# LCD4_3.net
KiCad netlist of a schematic drawn in Altium Designer
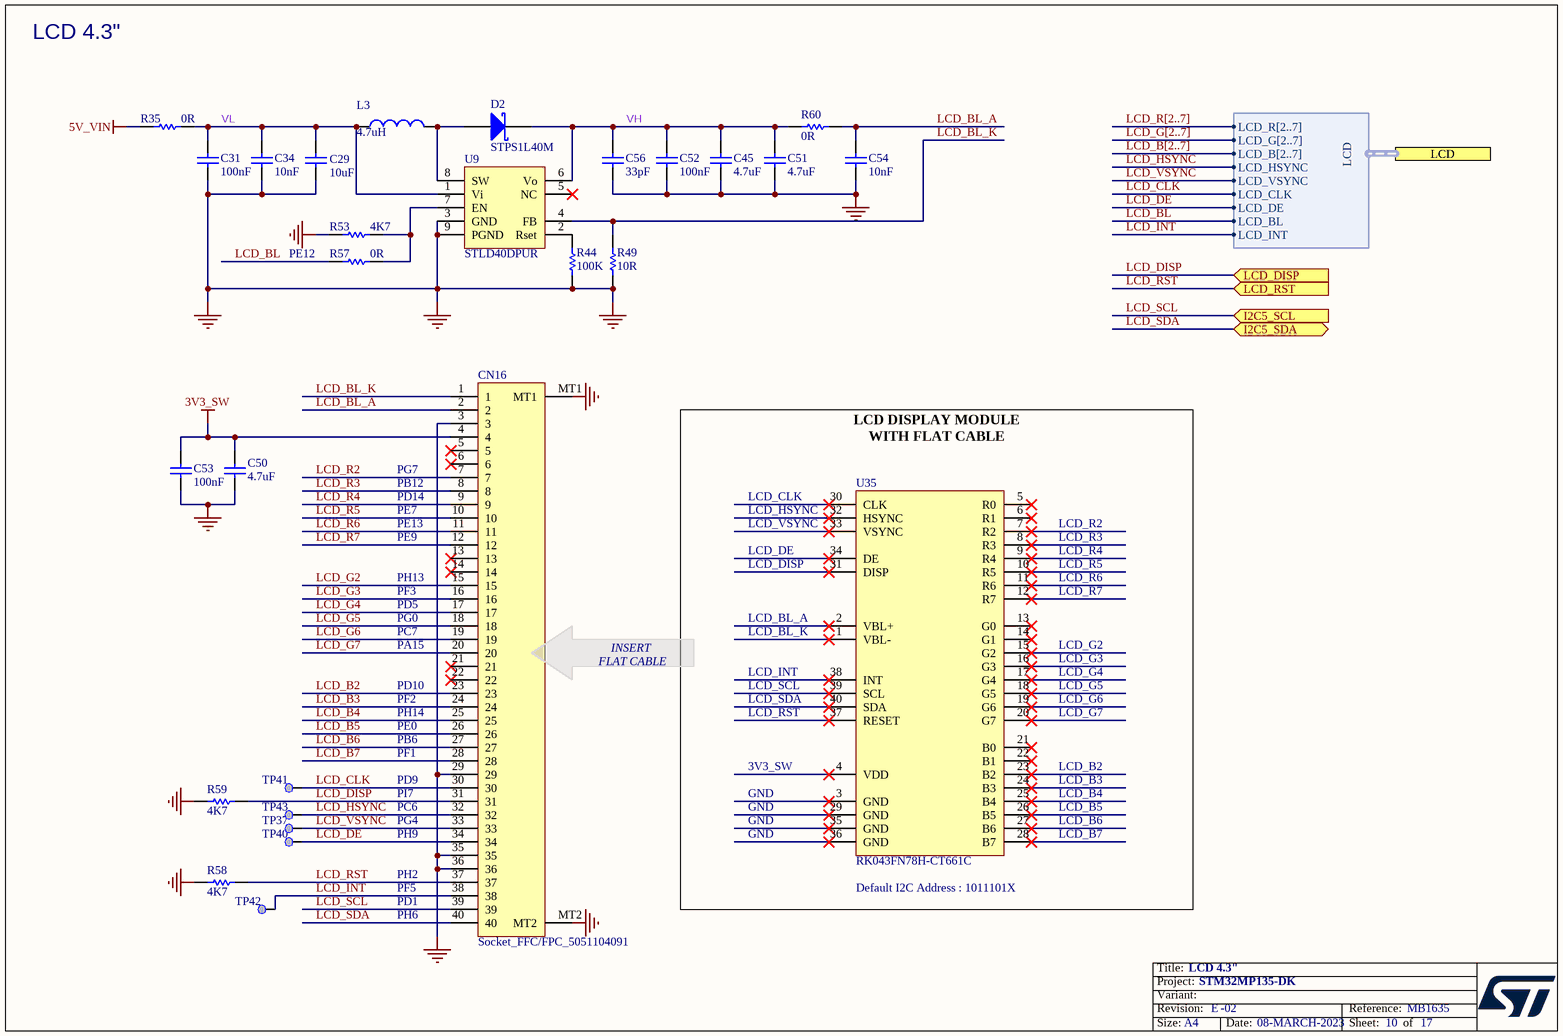
[diagram p0: LCD4.3.SchDoc]

(export (version "E")
  (design (tool "Eeschema 10.0.6"))
  (components
    (comp (ref "C29")
      (value "10uF")
      (footprint "C0603")
      (description "Capacitor, MLCC, 10uF, 10V, X5R, +/-10%, 0603, T=0.8mm")
      (fields
        (field (name "INTERNAL_PART_NUMBER") "MCD-00099")
        (field (name "MANUFACTURER_PART_NUMBER") "GRM188R61A106KE69D")
      )
      (libsource (lib "MCD_PARTS_database") (part "Capacitor"))
    )
    (comp (ref "C31")
      (value "100nF")
      (footprint "C0402")
      (description "Capacitor, MLCC, 100nF, 16V, X7R, +/-10%, 0402, T=0.5mm")
      (fields
        (field (name "INTERNAL_PART_NUMBER") "MCD-00006")
        (field (name "MANUFACTURER_PART_NUMBER") "CC0402KRX7R7BB104")
      )
      (libsource (lib "MCD_PARTS_database") (part "Capacitor"))
    )
    (comp (ref "C34")
      (value "10nF")
      (footprint "C0402")
      (description "Capacitor, MLCC, 10nF, 50V, X7R, +/-10%, 0402, T=0.5mm")
      (fields
        (field (name "INTERNAL_PART_NUMBER") "MCD-02198")
        (field (name "MANUFACTURER_PART_NUMBER") "CC0402KRX7R9BB103")
      )
      (libsource (lib "MCD_PARTS_database") (part "Capacitor"))
    )
    (comp (ref "C45")
      (value "4.7uF")
      (footprint "C1206_H1P25")
      (description "Capacitor, MLCC, 4.7uF, 50V, X7R, +/-10%, 1206, T=1.27mm")
      (fields
        (field (name "INTERNAL_PART_NUMBER") "MCD-00013")
        (field (name "MANUFACTURER_PART_NUMBER") "12065C475KAT2A")
      )
      (libsource (lib "MCD_PARTS_database") (part "Capacitor"))
    )
    (comp (ref "C50")
      (value "4.7uF")
      (footprint "C0402")
      (description "Capacitor, MLCC, 4.7uF, 6V3, X5R, +/-20%, 0402, T=0.5mm")
      (fields
        (field (name "INTERNAL_PART_NUMBER") "MCD-01356")
        (field (name "MANUFACTURER_PART_NUMBER") "GRM155R60J475ME47")
      )
      (libsource (lib "MCD_PARTS_database") (part "Capacitor"))
    )
    (comp (ref "C51")
      (value "4.7uF")
      (footprint "C1206_H1P25")
      (description "Capacitor, MLCC, 4.7uF, 50V, X7R, +/-10%, 1206, T=1.27mm")
      (fields
        (field (name "INTERNAL_PART_NUMBER") "MCD-00013")
        (field (name "MANUFACTURER_PART_NUMBER") "12065C475KAT2A")
      )
      (libsource (lib "MCD_PARTS_database") (part "Capacitor"))
    )
    (comp (ref "C52")
      (value "100nF")
      (footprint "C0603")
      (description "Capacitor, MLCC, 100nF, 50V, X7R, +/-10%, 0603, T=0.8mm")
      (fields (field (name "INTERNAL_PART_NUMBER") "MCD-01099") (field (name "BMS_PART_NUMBER") "9142278"))
      (libsource (lib "MCD_PARTS_database") (part "Capacitor"))
    )
    (comp (ref "C53")
      (value "100nF")
      (footprint "C0402")
      (description "Capacitor, MLCC, 100nF, 16V, X7R, +/-10%, 0402, T=0.5mm")
      (fields
        (field (name "INTERNAL_PART_NUMBER") "MCD-00006")
        (field (name "MANUFACTURER_PART_NUMBER") "CC0402KRX7R7BB104")
      )
      (libsource (lib "MCD_PARTS_database") (part "Capacitor"))
    )
    (comp (ref "C54")
      (value "10nF")
      (footprint "C0402")
      (description "Capacitor, MLCC, 10nF, 50V, X7R, +/-10%, 0402, T=0.5mm")
      (fields
        (field (name "INTERNAL_PART_NUMBER") "MCD-02198")
        (field (name "MANUFACTURER_PART_NUMBER") "CC0402KRX7R9BB103")
      )
      (libsource (lib "MCD_PARTS_database") (part "Capacitor"))
    )
    (comp (ref "C56")
      (value "33pF")
      (footprint "C0402")
      (description "Capacitor, MLCC, 33pF, 50V, NPO,+/-5%, 0402, T=0.5mm")
      (fields (field (name "INTERNAL_PART_NUMBER") "MCD-00277") (field (name "MANUFACTURER") "YAGEO"))
      (libsource (lib "MCD_PARTS_database") (part "Capacitor"))
    )
    (comp (ref "CN16")
      (value "Socket_FFC/FPC_5051104091")
      (footprint "CON_MOLEX_5051104091")
      (description "Socket_FFC/FPC, 40pins, 0.5mm, RA, SMD, T=1.9mm")
      (fields (field (name "INTERNAL_PART_NUMBER") "MCD-02589") (field (name "MANUFACTURER") "MOLEX"))
      (libsource (lib "MCD_PARTS_database") (part "5051104091"))
    )
    (comp (ref "D2")
      (value "STPS1L40M")
      (footprint "DIO_DO216-AA")
      (description "Low Drop power Schottky rectifier(1A, 40V, 0.4V)")
      (fields
        (field (name "INTERNAL_PART_NUMBER") "MCD-00033")
        (field (name "MANUFACTURER") "STMICROELECTRONICS")
      )
      (libsource (lib "MCD_PARTS_database") (part "STPS1L40M"))
    )
    (comp (ref "L3")
      (value "4.7uH")
      (footprint "L1210_LQH")
      (description "Inductor, 4.7uH, +/-30%, 1A, 180mR, 1210, T=1.7mm")
      (fields
        (field (name "INTERNAL_PART_NUMBER") "MCD-00048")
        (field (name "MANUFACTURER_PART_NUMBER") "LQH32PN4R7NN0L")
      )
      (libsource (lib "MCD_PARTS_database") (part "Inductor"))
    )
    (comp (ref "R35")
      (value "0R")
      (footprint "R0603")
      (description "Resistor, 0R, 0603, +/- 0.5mR, 1/4W")
      (fields (field (name "INTERNAL_PART_NUMBER") "MCD-00181") (field (name "MANUFACTURER") "ROHM"))
      (libsource (lib "MCD_PARTS_database") (part "Resistor"))
    )
    (comp (ref "R44")
      (value "100K")
      (footprint "R0402")
      (description "Resistor, 100K, 0402, +/-1%, 1/16W")
      (fields
        (field (name "INTERNAL_PART_NUMBER") "MCD-00059")
        (field (name "MANUFACTURER_PART_NUMBER") "RC0402FR-07100KL")
      )
      (libsource (lib "MCD_PARTS_database") (part "Resistor"))
    )
    (comp (ref "R49")
      (value "10R")
      (footprint "R0603")
      (description "Resistor, 10R, 0603, +/-1%, 1/4W")
      (fields
        (field (name "INTERNAL_PART_NUMBER") "MCD-00060")
        (field (name "MANUFACTURER_PART_NUMBER") "ESR03EZPF10R0")
      )
      (libsource (lib "MCD_PARTS_database") (part "Resistor"))
    )
    (comp (ref "R53")
      (value "4K7")
      (footprint "R0402")
      (description "Resistor, 4K7, 0402, +/-1%, 1/16W")
      (fields
        (field (name "INTERNAL_PART_NUMBER") "MCD-00065")
        (field (name "MANUFACTURER_PART_NUMBER") "RC0402FR-074K7L")
      )
      (libsource (lib "MCD_PARTS_database") (part "Resistor"))
    )
    (comp (ref "R57")
      (value "0R")
      (footprint "R0402")
      (description "Resistor, 0R, 0402, +/-5%, 1/16W")
      (fields
        (field (name "INTERNAL_PART_NUMBER") "MCD-00052")
        (field (name "MANUFACTURER_PART_NUMBER") "RC0402JR-070RL")
      )
      (libsource (lib "MCD_PARTS_database") (part "Resistor"))
    )
    (comp (ref "R58")
      (value "4K7")
      (footprint "R0402")
      (description "Resistor, 4K7, 0402, +/-1%, 1/16W")
      (fields
        (field (name "INTERNAL_PART_NUMBER") "MCD-00065")
        (field (name "MANUFACTURER_PART_NUMBER") "RC0402FR-074K7L")
      )
      (libsource (lib "MCD_PARTS_database") (part "Resistor"))
    )
    (comp (ref "R59")
      (value "4K7")
      (footprint "R0402")
      (description "Resistor, 4K7, 0402, +/-1%, 1/16W")
      (fields
        (field (name "INTERNAL_PART_NUMBER") "MCD-00065")
        (field (name "MANUFACTURER_PART_NUMBER") "RC0402FR-074K7L")
      )
      (libsource (lib "MCD_PARTS_database") (part "Resistor"))
    )
    (comp (ref "R60")
      (value "0R")
      (footprint "R0402")
      (description "Resistor, 0R, 0402, +/-5%, 1/16W")
      (fields (field (name "INTERNAL_PART_NUMBER") "MCD-00052") (field (name "MANUFACTURER") "YAGEO"))
      (libsource (lib "MCD_PARTS_database") (part "Resistor"))
    )
    (comp (ref "TP37")
      (value "Test Point")
      (footprint "TP_SMD_1MM")
      (description "Test Point 1mm")
      (fields (field (name "INTERNAL_PART_NUMBER") "MCD-00074"))
      (libsource (lib "MCD_PARTS_database") (part "Test Point"))
    )
    (comp (ref "TP40")
      (value "Test Point")
      (footprint "TP_SMD_1MM")
      (description "Test Point 1mm")
      (fields (field (name "INTERNAL_PART_NUMBER") "MCD-00074"))
      (libsource (lib "MCD_PARTS_database") (part "Test Point"))
    )
    (comp (ref "TP41")
      (value "Test Point")
      (footprint "TP_SMD_1MM")
      (description "Test Point 1mm")
      (fields (field (name "INTERNAL_PART_NUMBER") "MCD-00074"))
      (libsource (lib "MCD_PARTS_database") (part "Test Point"))
    )
    (comp (ref "TP42")
      (value "Test Point")
      (footprint "TP_SMD_1MM")
      (description "Test Point 1mm")
      (fields (field (name "INTERNAL_PART_NUMBER") "MCD-00074"))
      (libsource (lib "MCD_PARTS_database") (part "Test Point"))
    )
    (comp (ref "TP43")
      (value "Test Point")
      (footprint "TP_SMD_1MM")
      (description "Test Point 1mm")
      (fields (field (name "INTERNAL_PART_NUMBER") "MCD-00074"))
      (libsource (lib "MCD_PARTS_database") (part "Test Point"))
    )
    (comp (ref "U9")
      (value "STLD40DPUR")
      (footprint "ICC_QFN8-EPAD_3X3_P065")
      (description "White LED power supply for large display backlight, QFN8")
      (fields
        (field (name "INTERNAL_PART_NUMBER") "MCD-00082")
        (field (name "MANUFACTURER") "STMICROELECTRONICS")
      )
      (libsource (lib "MCD_PARTS_database") (part "STLD40DPUR"))
    )
    (comp (ref "U35")
      (value "RK043FN78H-CT661C")
      (footprint "LCD_DRAWING_ROCKTEK_RK043FN78H-CT661C")
      (fields
        (field (name "INTERNAL_PART_NUMBER") "MCD-02422")
        (field (name "MANUFACTURER_PART_NUMBER") "RK043FN78HV-CT661C")
        (field (name "MANUFACTURER") "ROCKTECH")
      )
      (libsource (lib "MCD_PARTS_database") (part "RK043FN78H-CT661C"))
    )
  )
  (nets
    (net (code "2") (name "/LCD_B2") (class "Default")
      (node (ref "CN16") (pin "23") (pinfunction "23_23") (pintype "passive"))
    )
    (net (code "3") (name "/LCD_B3") (class "Default")
      (node (ref "CN16") (pin "24") (pinfunction "24_24") (pintype "passive"))
    )
    (net (code "4") (name "/LCD_B4") (class "Default")
      (node (ref "CN16") (pin "25") (pinfunction "25_25") (pintype "passive"))
    )
    (net (code "5") (name "/LCD_B5") (class "Default")
      (node (ref "CN16") (pin "26") (pinfunction "26_26") (pintype "passive"))
    )
    (net (code "6") (name "/LCD_B6") (class "Default")
      (node (ref "CN16") (pin "27") (pinfunction "27_27") (pintype "passive"))
    )
    (net (code "7") (name "/LCD_B7") (class "Default")
      (node (ref "CN16") (pin "28") (pinfunction "28_28") (pintype "passive"))
    )
    (net (code "8") (name "/LCD_BL") (class "Default")
      (node (ref "R57") (pin "1") (pinfunction "1_1") (pintype "passive"))
    )
    (net (code "9") (name "/LCD_BL_A") (class "Default")
      (node (ref "C54") (pin "2") (pinfunction "2_2") (pintype "passive"))
      (node (ref "CN16") (pin "2") (pinfunction "2_2") (pintype "passive"))
      (node (ref "R60") (pin "2") (pinfunction "2_2") (pintype "passive"))
    )
    (net (code "10") (name "/LCD_BL_K") (class "Default")
      (node (ref "CN16") (pin "1") (pinfunction "1_1") (pintype "passive"))
      (node (ref "R49") (pin "2") (pinfunction "2_2") (pintype "passive"))
      (node (ref "U9") (pin "4") (pinfunction "FB_4") (pintype "passive"))
    )
    (net (code "12") (name "/LCD_CLK") (class "Default")
      (node (ref "CN16") (pin "30") (pinfunction "30_30") (pintype "passive"))
      (node (ref "TP41") (pin "1") (pinfunction "1_1") (pintype "passive"))
    )
    (net (code "13") (name "/LCD_DE") (class "Default")
      (node (ref "CN16") (pin "34") (pinfunction "34_34") (pintype "passive"))
      (node (ref "TP40") (pin "1") (pinfunction "1_1") (pintype "passive"))
    )
    (net (code "14") (name "/LCD_DISP") (class "Default")
      (node (ref "CN16") (pin "31") (pinfunction "31_31") (pintype "passive"))
      (node (ref "R59") (pin "2") (pinfunction "2_2") (pintype "passive"))
    )
    (net (code "15") (name "/LCD_G2") (class "Default")
      (node (ref "CN16") (pin "15") (pinfunction "15_15") (pintype "passive"))
    )
    (net (code "16") (name "/LCD_G3") (class "Default")
      (node (ref "CN16") (pin "16") (pinfunction "16_16") (pintype "passive"))
    )
    (net (code "17") (name "/LCD_G4") (class "Default")
      (node (ref "CN16") (pin "17") (pinfunction "17_17") (pintype "passive"))
    )
    (net (code "18") (name "/LCD_G5") (class "Default")
      (node (ref "CN16") (pin "18") (pinfunction "18_18") (pintype "passive"))
    )
    (net (code "19") (name "/LCD_G6") (class "Default")
      (node (ref "CN16") (pin "19") (pinfunction "19_19") (pintype "passive"))
    )
    (net (code "20") (name "/LCD_G7") (class "Default")
      (node (ref "CN16") (pin "20") (pinfunction "20_20") (pintype "passive"))
    )
    (net (code "21") (name "/LCD_HSYNC") (class "Default")
      (node (ref "CN16") (pin "32") (pinfunction "32_32") (pintype "passive"))
      (node (ref "TP43") (pin "1") (pinfunction "1_1") (pintype "passive"))
    )
    (net (code "22") (name "/LCD_INT") (class "Default")
      (node (ref "CN16") (pin "38") (pinfunction "38_38") (pintype "passive"))
      (node (ref "TP42") (pin "1") (pinfunction "1_1") (pintype "passive"))
    )
    (net (code "23") (name "/LCD_R2") (class "Default")
      (node (ref "CN16") (pin "7") (pinfunction "7_7") (pintype "passive"))
    )
    (net (code "24") (name "/LCD_R3") (class "Default")
      (node (ref "CN16") (pin "8") (pinfunction "8_8") (pintype "passive"))
    )
    (net (code "25") (name "/LCD_R4") (class "Default")
      (node (ref "CN16") (pin "9") (pinfunction "9_9") (pintype "passive"))
    )
    (net (code "26") (name "/LCD_R5") (class "Default")
      (node (ref "CN16") (pin "10") (pinfunction "10_10") (pintype "passive"))
    )
    (net (code "27") (name "/LCD_R6") (class "Default")
      (node (ref "CN16") (pin "11") (pinfunction "11_11") (pintype "passive"))
    )
    (net (code "28") (name "/LCD_R7") (class "Default")
      (node (ref "CN16") (pin "12") (pinfunction "12_12") (pintype "passive"))
    )
    (net (code "29") (name "/LCD_RST") (class "Default")
      (node (ref "CN16") (pin "37") (pinfunction "37_37") (pintype "passive"))
      (node (ref "R58") (pin "1") (pinfunction "1_1") (pintype "passive"))
    )
    (net (code "31") (name "/LCD_SCL") (class "Default")
      (node (ref "CN16") (pin "39") (pinfunction "39_39") (pintype "passive"))
    )
    (net (code "32") (name "/LCD_SDA") (class "Default")
      (node (ref "CN16") (pin "40") (pinfunction "40_40") (pintype "passive"))
    )
    (net (code "33") (name "/LCD_VSYNC") (class "Default")
      (node (ref "CN16") (pin "33") (pinfunction "33_33") (pintype "passive"))
      (node (ref "TP37") (pin "1") (pinfunction "1_1") (pintype "passive"))
    )
    (net (code "35") (name "/VH") (class "Default")
      (node (ref "C45") (pin "2") (pinfunction "2_2") (pintype "passive"))
      (node (ref "C51") (pin "2") (pinfunction "2_2") (pintype "passive"))
      (node (ref "C52") (pin "2") (pinfunction "2_2") (pintype "passive"))
      (node (ref "C56") (pin "2") (pinfunction "2_2") (pintype "passive"))
      (node (ref "D2") (pin "2") (pinfunction "K_2") (pintype "passive"))
      (node (ref "R60") (pin "1") (pinfunction "1_1") (pintype "passive"))
      (node (ref "U9") (pin "6") (pinfunction "Vo_6") (pintype "passive"))
    )
    (net (code "36") (name "/VL") (class "Default")
      (node (ref "C29") (pin "1") (pinfunction "1_1") (pintype "passive"))
      (node (ref "C31") (pin "2") (pinfunction "2_2") (pintype "passive"))
      (node (ref "C34") (pin "2") (pinfunction "2_2") (pintype "passive"))
      (node (ref "L3") (pin "1") (pinfunction "1_1") (pintype "passive"))
      (node (ref "R35") (pin "2") (pinfunction "2_2") (pintype "passive"))
      (node (ref "U9") (pin "1") (pinfunction "Vi_1") (pintype "passive"))
    )
    (net (code "38") (name "3V3_SW") (class "Default")
      (node (ref "C50") (pin "1") (pinfunction "1_1") (pintype "passive"))
      (node (ref "C53") (pin "2") (pinfunction "2_2") (pintype "passive"))
      (node (ref "CN16") (pin "4") (pinfunction "4_4") (pintype "passive"))
    )
    (net (code "39") (name "5V_VIN") (class "Default")
      (node (ref "R35") (pin "1") (pinfunction "1_1") (pintype "passive"))
    )
    (net (code "40") (name "GND") (class "Default")
      (node (ref "C29") (pin "2") (pinfunction "2_2") (pintype "passive"))
      (node (ref "C31") (pin "1") (pinfunction "1_1") (pintype "passive"))
      (node (ref "C34") (pin "1") (pinfunction "1_1") (pintype "passive"))
      (node (ref "C45") (pin "1") (pinfunction "1_1") (pintype "passive"))
      (node (ref "C50") (pin "2") (pinfunction "2_2") (pintype "passive"))
      (node (ref "C51") (pin "1") (pinfunction "1_1") (pintype "passive"))
      (node (ref "C52") (pin "1") (pinfunction "1_1") (pintype "passive"))
      (node (ref "C53") (pin "1") (pinfunction "1_1") (pintype "passive"))
      (node (ref "C54") (pin "1") (pinfunction "1_1") (pintype "passive"))
      (node (ref "C56") (pin "1") (pinfunction "1_1") (pintype "passive"))
      (node (ref "CN16") (pin "29") (pinfunction "29_29") (pintype "passive"))
      (node (ref "CN16") (pin "3") (pinfunction "3_3") (pintype "passive"))
      (node (ref "CN16") (pin "35") (pinfunction "35_35") (pintype "passive"))
      (node (ref "CN16") (pin "36") (pinfunction "36_36") (pintype "passive"))
      (node (ref "CN16") (pin "MT1") (pinfunction "MT1_MT1") (pintype "passive"))
      (node (ref "CN16") (pin "MT2") (pinfunction "MT2_MT2") (pintype "passive"))
      (node (ref "R44") (pin "1") (pinfunction "1_1") (pintype "passive"))
      (node (ref "R49") (pin "1") (pinfunction "1_1") (pintype "passive"))
      (node (ref "R53") (pin "1") (pinfunction "1_1") (pintype "passive"))
      (node (ref "R58") (pin "2") (pinfunction "2_2") (pintype "passive"))
      (node (ref "R59") (pin "1") (pinfunction "1_1") (pintype "passive"))
      (node (ref "U9") (pin "3") (pinfunction "GND_3") (pintype "passive"))
      (node (ref "U9") (pin "9") (pinfunction "PGND_9") (pintype "passive"))
    )
    (net (code "41") (name "Net-(D2-A)") (class "Default")
      (node (ref "D2") (pin "1") (pinfunction "A_1") (pintype "passive"))
      (node (ref "L3") (pin "2") (pinfunction "2_2") (pintype "passive"))
      (node (ref "U9") (pin "8") (pinfunction "SW_8") (pintype "passive"))
    )
    (net (code "42") (name "Net-(U9-EN)") (class "Default")
      (node (ref "R53") (pin "2") (pinfunction "2_2") (pintype "passive"))
      (node (ref "R57") (pin "2") (pinfunction "2_2") (pintype "passive"))
      (node (ref "U9") (pin "7") (pinfunction "EN_7") (pintype "passive"))
    )
    (net (code "43") (name "Net-(U9-Rset)") (class "Default")
      (node (ref "R44") (pin "2") (pinfunction "2_2") (pintype "passive"))
      (node (ref "U9") (pin "2") (pinfunction "Rset_2") (pintype "passive"))
    )
    (net (code "44") (name "unconnected-(CN16-Pad5)") (class "Default")
      (node (ref "CN16") (pin "5") (pinfunction "5_5") (pintype "passive+no_connect"))
    )
    (net (code "45") (name "unconnected-(CN16-Pad6)") (class "Default")
      (node (ref "CN16") (pin "6") (pinfunction "6_6") (pintype "passive+no_connect"))
    )
    (net (code "46") (name "unconnected-(CN16-Pad13)") (class "Default")
      (node (ref "CN16") (pin "13") (pinfunction "13_13") (pintype "passive+no_connect"))
    )
    (net (code "47") (name "unconnected-(CN16-Pad14)") (class "Default")
      (node (ref "CN16") (pin "14") (pinfunction "14_14") (pintype "passive+no_connect"))
    )
    (net (code "48") (name "unconnected-(CN16-Pad21)") (class "Default")
      (node (ref "CN16") (pin "21") (pinfunction "21_21") (pintype "passive+no_connect"))
    )
    (net (code "49") (name "unconnected-(CN16-Pad22)") (class "Default")
      (node (ref "CN16") (pin "22") (pinfunction "22_22") (pintype "passive+no_connect"))
    )
    (net (code "50") (name "unconnected-(U9-NC-Pad5)") (class "Default")
      (node (ref "U9") (pin "5") (pinfunction "NC_5") (pintype "passive+no_connect"))
    )
    (net (code "51") (name "unconnected-(U35-B0-Pad21)") (class "Default")
      (node (ref "U35") (pin "21") (pinfunction "B0_21") (pintype "passive+no_connect"))
    )
    (net (code "52") (name "unconnected-(U35-B1-Pad22)") (class "Default")
      (node (ref "U35") (pin "22") (pinfunction "B1_22") (pintype "passive+no_connect"))
    )
    (net (code "53") (name "unconnected-(U35-B2-Pad23)") (class "Default")
      (node (ref "U35") (pin "23") (pinfunction "B2_23") (pintype "passive+no_connect"))
    )
    (net (code "54") (name "unconnected-(U35-B3-Pad24)") (class "Default")
      (node (ref "U35") (pin "24") (pinfunction "B3_24") (pintype "passive+no_connect"))
    )
    (net (code "55") (name "unconnected-(U35-B4-Pad25)") (class "Default")
      (node (ref "U35") (pin "25") (pinfunction "B4_25") (pintype "passive+no_connect"))
    )
    (net (code "56") (name "unconnected-(U35-B5-Pad26)") (class "Default")
      (node (ref "U35") (pin "26") (pinfunction "B5_26") (pintype "passive+no_connect"))
    )
    (net (code "57") (name "unconnected-(U35-B6-Pad27)") (class "Default")
      (node (ref "U35") (pin "27") (pinfunction "B6_27") (pintype "passive+no_connect"))
    )
    (net (code "58") (name "unconnected-(U35-B7-Pad28)") (class "Default")
      (node (ref "U35") (pin "28") (pinfunction "B7_28") (pintype "passive+no_connect"))
    )
    (net (code "59") (name "unconnected-(U35-CLK-Pad30)") (class "Default")
      (node (ref "U35") (pin "30") (pinfunction "CLK_30") (pintype "passive+no_connect"))
    )
    (net (code "60") (name "unconnected-(U35-DE-Pad34)") (class "Default")
      (node (ref "U35") (pin "34") (pinfunction "DE_34") (pintype "passive+no_connect"))
    )
    (net (code "61") (name "unconnected-(U35-DISP-Pad31)") (class "Default")
      (node (ref "U35") (pin "31") (pinfunction "DISP_31") (pintype "passive+no_connect"))
    )
    (net (code "62") (name "unconnected-(U35-G0-Pad13)") (class "Default")
      (node (ref "U35") (pin "13") (pinfunction "G0_13") (pintype "passive+no_connect"))
    )
    (net (code "63") (name "unconnected-(U35-G1-Pad14)") (class "Default")
      (node (ref "U35") (pin "14") (pinfunction "G1_14") (pintype "passive+no_connect"))
    )
    (net (code "64") (name "unconnected-(U35-G2-Pad15)") (class "Default")
      (node (ref "U35") (pin "15") (pinfunction "G2_15") (pintype "passive+no_connect"))
    )
    (net (code "65") (name "unconnected-(U35-G3-Pad16)") (class "Default")
      (node (ref "U35") (pin "16") (pinfunction "G3_16") (pintype "passive+no_connect"))
    )
    (net (code "66") (name "unconnected-(U35-G4-Pad17)") (class "Default")
      (node (ref "U35") (pin "17") (pinfunction "G4_17") (pintype "passive+no_connect"))
    )
    (net (code "67") (name "unconnected-(U35-G5-Pad18)") (class "Default")
      (node (ref "U35") (pin "18") (pinfunction "G5_18") (pintype "passive+no_connect"))
    )
    (net (code "68") (name "unconnected-(U35-G6-Pad19)") (class "Default")
      (node (ref "U35") (pin "19") (pinfunction "G6_19") (pintype "passive+no_connect"))
    )
    (net (code "69") (name "unconnected-(U35-G7-Pad20)") (class "Default")
      (node (ref "U35") (pin "20") (pinfunction "G7_20") (pintype "passive+no_connect"))
    )
    (net (code "70") (name "unconnected-(U35-GND-Pad3)") (class "Default")
      (node (ref "U35") (pin "3") (pinfunction "GND_3") (pintype "passive+no_connect"))
    )
    (net (code "71") (name "unconnected-(U35-GND-Pad29)") (class "Default")
      (node (ref "U35") (pin "29") (pinfunction "GND_29") (pintype "passive+no_connect"))
    )
    (net (code "72") (name "unconnected-(U35-GND-Pad35)") (class "Default")
      (node (ref "U35") (pin "35") (pinfunction "GND_35") (pintype "passive+no_connect"))
    )
    (net (code "73") (name "unconnected-(U35-GND-Pad36)") (class "Default")
      (node (ref "U35") (pin "36") (pinfunction "GND_36") (pintype "passive+no_connect"))
    )
    (net (code "74") (name "unconnected-(U35-HSYNC-Pad32)") (class "Default")
      (node (ref "U35") (pin "32") (pinfunction "HSYNC_32") (pintype "passive+no_connect"))
    )
    (net (code "75") (name "unconnected-(U35-INT-Pad38)") (class "Default")
      (node (ref "U35") (pin "38") (pinfunction "INT_38") (pintype "passive+no_connect"))
    )
    (net (code "76") (name "unconnected-(U35-R0-Pad5)") (class "Default")
      (node (ref "U35") (pin "5") (pinfunction "R0_5") (pintype "passive+no_connect"))
    )
    (net (code "77") (name "unconnected-(U35-R1-Pad6)") (class "Default")
      (node (ref "U35") (pin "6") (pinfunction "R1_6") (pintype "passive+no_connect"))
    )
    (net (code "78") (name "unconnected-(U35-R2-Pad7)") (class "Default")
      (node (ref "U35") (pin "7") (pinfunction "R2_7") (pintype "passive+no_connect"))
    )
    (net (code "79") (name "unconnected-(U35-R3-Pad8)") (class "Default")
      (node (ref "U35") (pin "8") (pinfunction "R3_8") (pintype "passive+no_connect"))
    )
    (net (code "80") (name "unconnected-(U35-R4-Pad9)") (class "Default")
      (node (ref "U35") (pin "9") (pinfunction "R4_9") (pintype "passive+no_connect"))
    )
    (net (code "81") (name "unconnected-(U35-R5-Pad10)") (class "Default")
      (node (ref "U35") (pin "10") (pinfunction "R5_10") (pintype "passive+no_connect"))
    )
    (net (code "82") (name "unconnected-(U35-R6-Pad11)") (class "Default")
      (node (ref "U35") (pin "11") (pinfunction "R6_11") (pintype "passive+no_connect"))
    )
    (net (code "83") (name "unconnected-(U35-R7-Pad12)") (class "Default")
      (node (ref "U35") (pin "12") (pinfunction "R7_12") (pintype "passive+no_connect"))
    )
    (net (code "84") (name "unconnected-(U35-RESET-Pad37)") (class "Default")
      (node (ref "U35") (pin "37") (pinfunction "RESET_37") (pintype "passive+no_connect"))
    )
    (net (code "85") (name "unconnected-(U35-SCL-Pad39)") (class "Default")
      (node (ref "U35") (pin "39") (pinfunction "SCL_39") (pintype "passive+no_connect"))
    )
    (net (code "86") (name "unconnected-(U35-SDA-Pad40)") (class "Default")
      (node (ref "U35") (pin "40") (pinfunction "SDA_40") (pintype "passive+no_connect"))
    )
    (net (code "87") (name "unconnected-(U35-VBL+-Pad2)") (class "Default")
      (node (ref "U35") (pin "2") (pinfunction "VBL+_2") (pintype "passive+no_connect"))
    )
    (net (code "88") (name "unconnected-(U35-VBL--Pad1)") (class "Default")
      (node (ref "U35") (pin "1") (pinfunction "VBL-_1") (pintype "passive+no_connect"))
    )
    (net (code "89") (name "unconnected-(U35-VDD-Pad4)") (class "Default")
      (node (ref "U35") (pin "4") (pinfunction "VDD_4") (pintype "passive+no_connect"))
    )
    (net (code "90") (name "unconnected-(U35-VSYNC-Pad33)") (class "Default")
      (node (ref "U35") (pin "33") (pinfunction "VSYNC_33") (pintype "passive+no_connect"))
    )
  )
)
